# RelayArray.net
KiCad netlist of a schematic drawn in Altium Designer
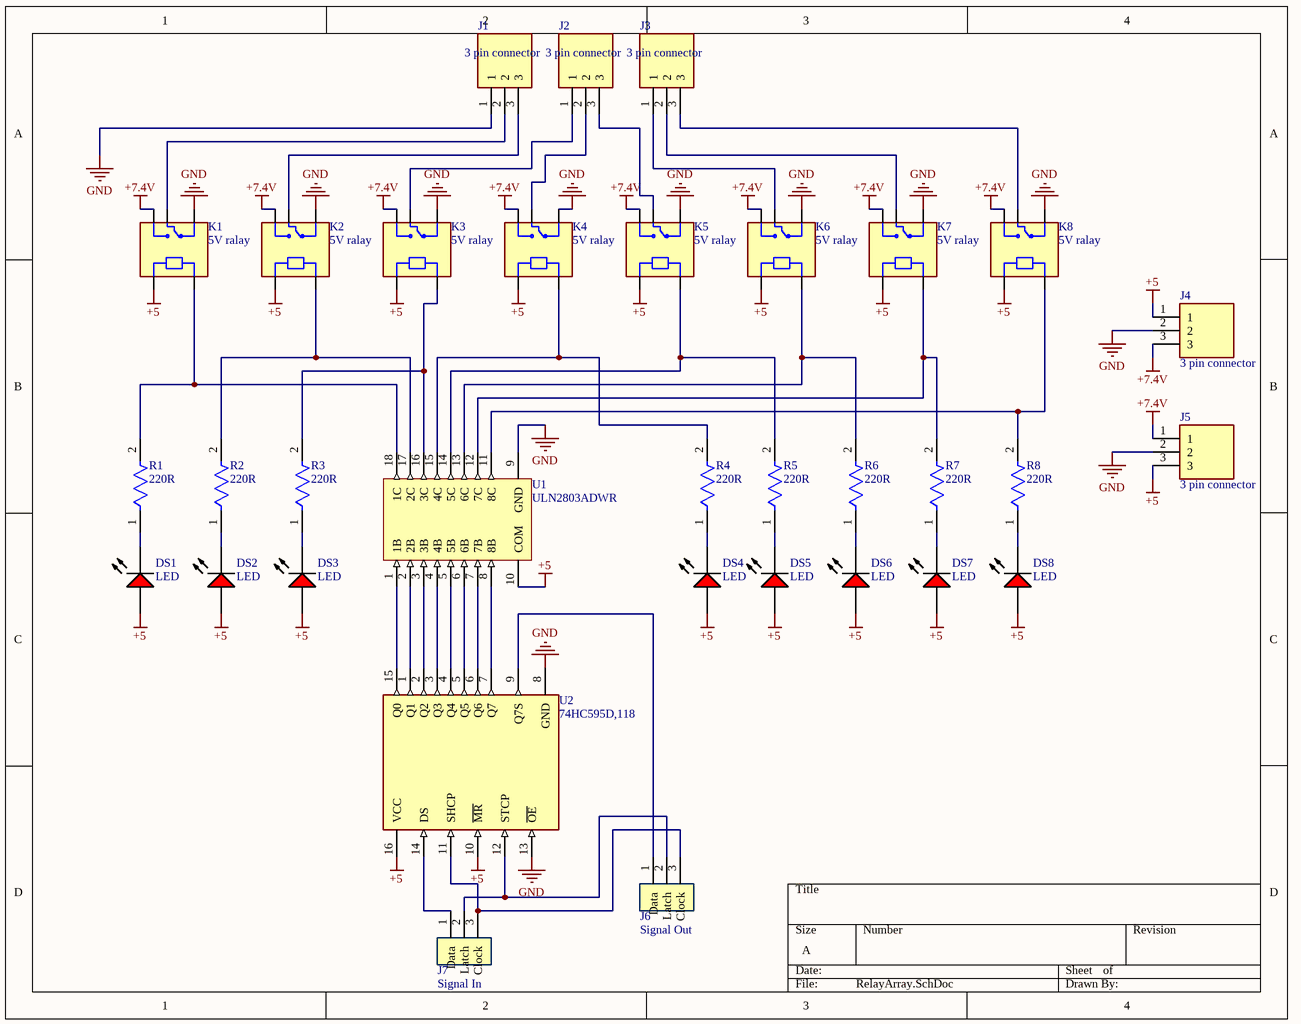
[diagram p0: RelayArray.SchDoc]

(export (version "E")
  (design (tool "Eeschema 10.0.6"))
  (components
    (comp (ref "DS1")
      (value "LED")
      (footprint "big red led")
      (description "T-1 3/4 (5 mm) Diffused LED Lamp, 1.9 V, -40 to 100 degC, 2-Pin THD, RoHS, Bulk")
      (fields (field (name "MANUFACTURER") "Avago"))
      (libsource (lib "Firework Detenator PCB") (part "big red led"))
    )
    (comp (ref "DS2")
      (value "LED")
      (footprint "big red led")
      (description "T-1 3/4 (5 mm) Diffused LED Lamp, 1.9 V, -40 to 100 degC, 2-Pin THD, RoHS, Bulk")
      (fields (field (name "MANUFACTURER") "Avago"))
      (libsource (lib "Firework Detenator PCB") (part "big red led"))
    )
    (comp (ref "DS3")
      (value "LED")
      (footprint "big red led")
      (description "T-1 3/4 (5 mm) Diffused LED Lamp, 1.9 V, -40 to 100 degC, 2-Pin THD, RoHS, Bulk")
      (fields (field (name "MANUFACTURER") "Avago"))
      (libsource (lib "Firework Detenator PCB") (part "big red led"))
    )
    (comp (ref "DS4")
      (value "LED")
      (footprint "big red led")
      (description "T-1 3/4 (5 mm) Diffused LED Lamp, 1.9 V, -40 to 100 degC, 2-Pin THD, RoHS, Bulk")
      (fields (field (name "MANUFACTURER") "Avago"))
      (libsource (lib "Firework Detenator PCB") (part "big red led"))
    )
    (comp (ref "DS5")
      (value "LED")
      (footprint "big red led")
      (description "T-1 3/4 (5 mm) Diffused LED Lamp, 1.9 V, -40 to 100 degC, 2-Pin THD, RoHS, Bulk")
      (fields (field (name "MANUFACTURER") "Avago"))
      (libsource (lib "Firework Detenator PCB") (part "big red led"))
    )
    (comp (ref "DS6")
      (value "LED")
      (footprint "big red led")
      (description "T-1 3/4 (5 mm) Diffused LED Lamp, 1.9 V, -40 to 100 degC, 2-Pin THD, RoHS, Bulk")
      (fields (field (name "MANUFACTURER") "Avago"))
      (libsource (lib "Firework Detenator PCB") (part "big red led"))
    )
    (comp (ref "DS7")
      (value "LED")
      (footprint "big red led")
      (description "T-1 3/4 (5 mm) Diffused LED Lamp, 1.9 V, -40 to 100 degC, 2-Pin THD, RoHS, Bulk")
      (fields (field (name "MANUFACTURER") "Avago"))
      (libsource (lib "Firework Detenator PCB") (part "big red led"))
    )
    (comp (ref "DS8")
      (value "LED")
      (footprint "big red led")
      (description "T-1 3/4 (5 mm) Diffused LED Lamp, 1.9 V, -40 to 100 degC, 2-Pin THD, RoHS, Bulk")
      (fields (field (name "MANUFACTURER") "Avago"))
      (libsource (lib "Firework Detenator PCB") (part "big red led"))
    )
    (comp (ref "J1")
      (value "3 pin connector")
      (footprint "3 pin connector")
      (description "3P,STRAIGHT,SIDE ENTRY,3.5MM")
      (fields (field (name "MF") "TE Connectivity") (field (name "MP") "1546551-3"))
      (libsource (lib "") (part "3 pin connector_1"))
    )
    (comp (ref "J2")
      (value "3 pin connector")
      (footprint "3 pin connector")
      (description "3P,STRAIGHT,SIDE ENTRY,3.5MM")
      (fields (field (name "MF") "TE Connectivity") (field (name "MP") "1546551-3"))
      (libsource (lib "") (part "3 pin connector_1"))
    )
    (comp (ref "J3")
      (value "3 pin connector")
      (footprint "3 pin connector")
      (description "3P,STRAIGHT,SIDE ENTRY,3.5MM")
      (fields (field (name "MF") "TE Connectivity") (field (name "MP") "1546551-3"))
      (libsource (lib "") (part "3 pin connector_1"))
    )
    (comp (ref "J4")
      (value "3 pin connector")
      (footprint "3 pin connector")
      (description "3P,STRAIGHT,SIDE ENTRY,3.5MM")
      (fields (field (name "MF") "TE Connectivity") (field (name "MP") "1546551-3"))
      (libsource (lib "Firework Detenator PCB") (part "3 pin connector"))
    )
    (comp (ref "J5")
      (value "3 pin connector")
      (footprint "3 pin connector")
      (description "3P,STRAIGHT,SIDE ENTRY,3.5MM")
      (fields (field (name "MF") "TE Connectivity") (field (name "MP") "1546551-3"))
      (libsource (lib "Firework Detenator PCB") (part "3 pin connector"))
    )
    (comp (ref "J6")
      (value "Signal Out")
      (footprint "3 pin header")
      (description "3P,STRAIGHT,SIDE ENTRY,3.5MM")
      (fields (field (name "MF") "TE Connectivity") (field (name "MP") "1546551-3"))
      (libsource (lib "Firework Detenator PCB") (part "3 pin header"))
    )
    (comp (ref "J7")
      (value "Signal In")
      (footprint "3 pin header")
      (description "3P,STRAIGHT,SIDE ENTRY,3.5MM")
      (fields (field (name "MF") "TE Connectivity") (field (name "MP") "1546551-3"))
      (libsource (lib "Firework Detenator PCB") (part "3 pin header"))
    )
    (comp (ref "K1")
      (value "5V ralay")
      (footprint "RELAY_SRD-05VDC-SL-C")
      (fields (field (name "MF") "Songle Relay") (field (name "MP") "SRD-05VDC-SL-C"))
      (libsource (lib "Firework Detenator PCB") (part "5V ralay"))
    )
    (comp (ref "K2")
      (value "5V ralay")
      (footprint "RELAY_SRD-05VDC-SL-C")
      (fields (field (name "MF") "Songle Relay") (field (name "MP") "SRD-05VDC-SL-C"))
      (libsource (lib "Firework Detenator PCB") (part "5V ralay"))
    )
    (comp (ref "K3")
      (value "5V ralay")
      (footprint "RELAY_SRD-05VDC-SL-C")
      (fields (field (name "MF") "Songle Relay") (field (name "MP") "SRD-05VDC-SL-C"))
      (libsource (lib "Firework Detenator PCB") (part "5V ralay"))
    )
    (comp (ref "K4")
      (value "5V ralay")
      (footprint "RELAY_SRD-05VDC-SL-C")
      (fields (field (name "MF") "Songle Relay") (field (name "MP") "SRD-05VDC-SL-C"))
      (libsource (lib "Firework Detenator PCB") (part "5V ralay"))
    )
    (comp (ref "K5")
      (value "5V ralay")
      (footprint "RELAY_SRD-05VDC-SL-C")
      (fields (field (name "MF") "Songle Relay") (field (name "MP") "SRD-05VDC-SL-C"))
      (libsource (lib "Firework Detenator PCB") (part "5V ralay"))
    )
    (comp (ref "K6")
      (value "5V ralay")
      (footprint "RELAY_SRD-05VDC-SL-C")
      (fields (field (name "MF") "Songle Relay") (field (name "MP") "SRD-05VDC-SL-C"))
      (libsource (lib "Firework Detenator PCB") (part "5V ralay"))
    )
    (comp (ref "K7")
      (value "5V ralay")
      (footprint "RELAY_SRD-05VDC-SL-C")
      (fields (field (name "MF") "Songle Relay") (field (name "MP") "SRD-05VDC-SL-C"))
      (libsource (lib "Firework Detenator PCB") (part "5V ralay"))
    )
    (comp (ref "K8")
      (value "5V ralay")
      (footprint "RELAY_SRD-05VDC-SL-C")
      (fields (field (name "MF") "Songle Relay") (field (name "MP") "SRD-05VDC-SL-C"))
      (libsource (lib "Firework Detenator PCB") (part "5V ralay"))
    )
    (comp (ref "R1")
      (value "220R")
      (footprint "FP-CRCW0805-e3-IPC_A")
      (description "RES Thick Film, 220Ω, 1%, 0.125W, 100ppm/°C, 0805")
      (fields (field (name "TOLERANCE") "1%"))
      (libsource (lib "Altium Content Vault") (part "1029c3af85768c4190bb7ad29bc67b5"))
    )
    (comp (ref "R2")
      (value "220R")
      (footprint "FP-CRCW0805-e3-IPC_A")
      (description "RES Thick Film, 220Ω, 1%, 0.125W, 100ppm/°C, 0805")
      (fields (field (name "TOLERANCE") "1%"))
      (libsource (lib "Altium Content Vault") (part "1029c3af85768c4190bb7ad29bc67b5"))
    )
    (comp (ref "R3")
      (value "220R")
      (footprint "FP-CRCW0805-e3-IPC_A")
      (description "RES Thick Film, 220Ω, 1%, 0.125W, 100ppm/°C, 0805")
      (fields (field (name "TOLERANCE") "1%"))
      (libsource (lib "Altium Content Vault") (part "1029c3af85768c4190bb7ad29bc67b5"))
    )
    (comp (ref "R4")
      (value "220R")
      (footprint "FP-CRCW0805-e3-IPC_A")
      (description "RES Thick Film, 220Ω, 1%, 0.125W, 100ppm/°C, 0805")
      (fields (field (name "TOLERANCE") "1%"))
      (libsource (lib "Altium Content Vault") (part "1029c3af85768c4190bb7ad29bc67b5"))
    )
    (comp (ref "R5")
      (value "220R")
      (footprint "FP-CRCW0805-e3-IPC_A")
      (description "RES Thick Film, 220Ω, 1%, 0.125W, 100ppm/°C, 0805")
      (fields (field (name "TOLERANCE") "1%"))
      (libsource (lib "Altium Content Vault") (part "1029c3af85768c4190bb7ad29bc67b5"))
    )
    (comp (ref "R6")
      (value "220R")
      (footprint "FP-CRCW0805-e3-IPC_A")
      (description "RES Thick Film, 220Ω, 1%, 0.125W, 100ppm/°C, 0805")
      (fields (field (name "TOLERANCE") "1%"))
      (libsource (lib "Altium Content Vault") (part "1029c3af85768c4190bb7ad29bc67b5"))
    )
    (comp (ref "R7")
      (value "220R")
      (footprint "FP-CRCW0805-e3-IPC_A")
      (description "RES Thick Film, 220Ω, 1%, 0.125W, 100ppm/°C, 0805")
      (fields (field (name "TOLERANCE") "1%"))
      (libsource (lib "Altium Content Vault") (part "1029c3af85768c4190bb7ad29bc67b5"))
    )
    (comp (ref "R8")
      (value "220R")
      (footprint "FP-CRCW0805-e3-IPC_A")
      (description "RES Thick Film, 220Ω, 1%, 0.125W, 100ppm/°C, 0805")
      (fields (field (name "TOLERANCE") "1%"))
      (libsource (lib "Altium Content Vault") (part "1029c3af85768c4190bb7ad29bc67b5"))
    )
    (comp (ref "U1")
      (value "ULN2803ADWR")
      (footprint "DW0018A_L")
      (fields (field (name "MANUFACTURER") "Texas Instruments") (field (name "PARTNUMBER") "ULN2803A"))
      (libsource (lib "Altium Content Vault") (part "TI-ULN2803A-SOIC_DW-18"))
    )
    (comp (ref "U2")
      (value "74HC595D,118")
      (footprint "FP-SOT109-1-IPC_C")
      (description "IC SHIFT REGISTER 8BIT 16SOIC")
      (libsource (lib "Altium Content Vault") (part "7b153f231cfcc3ac06dee253bd56617"))
    )
  )
  (nets
    (net (code "1") (name "+5") (class "Default")
      (node (ref "DS1") (pin "1") (pinfunction "A_1") (pintype "passive"))
      (node (ref "DS2") (pin "1") (pinfunction "A_1") (pintype "passive"))
      (node (ref "DS3") (pin "1") (pinfunction "A_1") (pintype "passive"))
      (node (ref "DS4") (pin "1") (pinfunction "A_1") (pintype "passive"))
      (node (ref "DS5") (pin "1") (pinfunction "A_1") (pintype "passive"))
      (node (ref "DS6") (pin "1") (pinfunction "A_1") (pintype "passive"))
      (node (ref "DS7") (pin "1") (pinfunction "A_1") (pintype "passive"))
      (node (ref "DS8") (pin "1") (pinfunction "A_1") (pintype "passive"))
      (node (ref "J4") (pin "1") (pinfunction "1_1") (pintype "passive"))
      (node (ref "J5") (pin "3") (pinfunction "3_3") (pintype "passive"))
      (node (ref "K1") (pin "A1") (pinfunction "A1_A1") (pintype "passive"))
      (node (ref "K2") (pin "A1") (pinfunction "A1_A1") (pintype "passive"))
      (node (ref "K3") (pin "A1") (pinfunction "A1_A1") (pintype "passive"))
      (node (ref "K4") (pin "A1") (pinfunction "A1_A1") (pintype "passive"))
      (node (ref "K5") (pin "A1") (pinfunction "A1_A1") (pintype "passive"))
      (node (ref "K6") (pin "A1") (pinfunction "A1_A1") (pintype "passive"))
      (node (ref "K7") (pin "A1") (pinfunction "A1_A1") (pintype "passive"))
      (node (ref "K8") (pin "A1") (pinfunction "A1_A1") (pintype "passive"))
      (node (ref "U1") (pin "10") (pinfunction "COM_10") (pintype "passive"))
      (node (ref "U2") (pin "10") (pinfunction "~{MR}_10") (pintype "input"))
      (node (ref "U2") (pin "16") (pinfunction "VCC_16") (pintype "power_in"))
    )
    (net (code "2") (name "+7.4V") (class "Default")
      (node (ref "J4") (pin "3") (pinfunction "3_3") (pintype "passive"))
      (node (ref "J5") (pin "1") (pinfunction "1_1") (pintype "passive"))
      (node (ref "K1") (pin "NO") (pinfunction "NO_NO") (pintype "passive"))
      (node (ref "K2") (pin "NO") (pinfunction "NO_NO") (pintype "passive"))
      (node (ref "K3") (pin "NO") (pinfunction "NO_NO") (pintype "passive"))
      (node (ref "K4") (pin "NO") (pinfunction "NO_NO") (pintype "passive"))
      (node (ref "K5") (pin "NO") (pinfunction "NO_NO") (pintype "passive"))
      (node (ref "K6") (pin "NO") (pinfunction "NO_NO") (pintype "passive"))
      (node (ref "K7") (pin "NO") (pinfunction "NO_NO") (pintype "passive"))
      (node (ref "K8") (pin "NO") (pinfunction "NO_NO") (pintype "passive"))
    )
    (net (code "3") (name "GND") (class "Default")
      (node (ref "J1") (pin "1") (pinfunction "1_1") (pintype "passive"))
      (node (ref "J4") (pin "2") (pinfunction "2_2") (pintype "passive"))
      (node (ref "J5") (pin "2") (pinfunction "2_2") (pintype "passive"))
      (node (ref "K1") (pin "NC") (pinfunction "NC_NC") (pintype "passive"))
      (node (ref "K2") (pin "NC") (pinfunction "NC_NC") (pintype "passive"))
      (node (ref "K3") (pin "NC") (pinfunction "NC_NC") (pintype "passive"))
      (node (ref "K4") (pin "NC") (pinfunction "NC_NC") (pintype "passive"))
      (node (ref "K5") (pin "NC") (pinfunction "NC_NC") (pintype "passive"))
      (node (ref "K6") (pin "NC") (pinfunction "NC_NC") (pintype "passive"))
      (node (ref "K7") (pin "NC") (pinfunction "NC_NC") (pintype "passive"))
      (node (ref "K8") (pin "NC") (pinfunction "NC_NC") (pintype "passive"))
      (node (ref "U1") (pin "9") (pinfunction "GND_9") (pintype "power_in"))
      (node (ref "U2") (pin "13") (pinfunction "~{OE}_13") (pintype "input"))
      (node (ref "U2") (pin "8") (pinfunction "GND_8") (pintype "power_in"))
    )
    (net (code "4") (name "Net-(DS1-K)") (class "Default")
      (node (ref "DS1") (pin "2") (pinfunction "K_2") (pintype "passive"))
      (node (ref "R1") (pin "1") (pinfunction "1_1") (pintype "passive"))
    )
    (net (code "5") (name "Net-(DS2-K)") (class "Default")
      (node (ref "DS2") (pin "2") (pinfunction "K_2") (pintype "passive"))
      (node (ref "R2") (pin "1") (pinfunction "1_1") (pintype "passive"))
    )
    (net (code "6") (name "Net-(DS3-K)") (class "Default")
      (node (ref "DS3") (pin "2") (pinfunction "K_2") (pintype "passive"))
      (node (ref "R3") (pin "1") (pinfunction "1_1") (pintype "passive"))
    )
    (net (code "7") (name "Net-(DS4-K)") (class "Default")
      (node (ref "DS4") (pin "2") (pinfunction "K_2") (pintype "passive"))
      (node (ref "R4") (pin "1") (pinfunction "1_1") (pintype "passive"))
    )
    (net (code "8") (name "Net-(DS5-K)") (class "Default")
      (node (ref "DS5") (pin "2") (pinfunction "K_2") (pintype "passive"))
      (node (ref "R5") (pin "1") (pinfunction "1_1") (pintype "passive"))
    )
    (net (code "9") (name "Net-(DS6-K)") (class "Default")
      (node (ref "DS6") (pin "2") (pinfunction "K_2") (pintype "passive"))
      (node (ref "R6") (pin "1") (pinfunction "1_1") (pintype "passive"))
    )
    (net (code "10") (name "Net-(DS7-K)") (class "Default")
      (node (ref "DS7") (pin "2") (pinfunction "K_2") (pintype "passive"))
      (node (ref "R7") (pin "1") (pinfunction "1_1") (pintype "passive"))
    )
    (net (code "11") (name "Net-(DS8-K)") (class "Default")
      (node (ref "DS8") (pin "2") (pinfunction "K_2") (pintype "passive"))
      (node (ref "R8") (pin "1") (pinfunction "1_1") (pintype "passive"))
    )
    (net (code "12") (name "Net-(J1-Pad2)") (class "Default")
      (node (ref "J1") (pin "2") (pinfunction "2_2") (pintype "passive"))
      (node (ref "K1") (pin "COM") (pinfunction "COM_COM") (pintype "passive"))
    )
    (net (code "13") (name "Net-(J1-Pad3)") (class "Default")
      (node (ref "J1") (pin "3") (pinfunction "3_3") (pintype "passive"))
      (node (ref "K2") (pin "COM") (pinfunction "COM_COM") (pintype "passive"))
    )
    (net (code "14") (name "Net-(J2-Pad1)") (class "Default")
      (node (ref "J2") (pin "1") (pinfunction "1_1") (pintype "passive"))
      (node (ref "K3") (pin "COM") (pinfunction "COM_COM") (pintype "passive"))
    )
    (net (code "15") (name "Net-(J2-Pad2)") (class "Default")
      (node (ref "J2") (pin "2") (pinfunction "2_2") (pintype "passive"))
      (node (ref "K4") (pin "COM") (pinfunction "COM_COM") (pintype "passive"))
    )
    (net (code "16") (name "Net-(J2-Pad3)") (class "Default")
      (node (ref "J2") (pin "3") (pinfunction "3_3") (pintype "passive"))
      (node (ref "K5") (pin "COM") (pinfunction "COM_COM") (pintype "passive"))
    )
    (net (code "17") (name "Net-(J3-Pad1)") (class "Default")
      (node (ref "J3") (pin "1") (pinfunction "1_1") (pintype "passive"))
      (node (ref "K6") (pin "COM") (pinfunction "COM_COM") (pintype "passive"))
    )
    (net (code "18") (name "Net-(J3-Pad2)") (class "Default")
      (node (ref "J3") (pin "2") (pinfunction "2_2") (pintype "passive"))
      (node (ref "K7") (pin "COM") (pinfunction "COM_COM") (pintype "passive"))
    )
    (net (code "19") (name "Net-(J3-Pad3)") (class "Default")
      (node (ref "J3") (pin "3") (pinfunction "3_3") (pintype "passive"))
      (node (ref "K8") (pin "COM") (pinfunction "COM_COM") (pintype "passive"))
    )
    (net (code "20") (name "Net-(J6-Clock)") (class "Default")
      (node (ref "J6") (pin "3") (pinfunction "Clock_3") (pintype "passive"))
      (node (ref "J7") (pin "3") (pinfunction "Clock_3") (pintype "passive"))
      (node (ref "U2") (pin "11") (pinfunction "SHCP_11") (pintype "input"))
    )
    (net (code "21") (name "Net-(J6-Data)") (class "Default")
      (node (ref "J6") (pin "1") (pinfunction "Data_1") (pintype "passive"))
      (node (ref "U2") (pin "9") (pinfunction "Q7S_9") (pintype "output"))
    )
    (net (code "22") (name "Net-(J6-Latch)") (class "Default")
      (node (ref "J6") (pin "2") (pinfunction "Latch_2") (pintype "passive"))
      (node (ref "J7") (pin "2") (pinfunction "Latch_2") (pintype "passive"))
      (node (ref "U2") (pin "12") (pinfunction "STCP_12") (pintype "input"))
    )
    (net (code "23") (name "Net-(J7-Data)") (class "Default")
      (node (ref "J7") (pin "1") (pinfunction "Data_1") (pintype "passive"))
      (node (ref "U2") (pin "14") (pinfunction "DS_14") (pintype "input"))
    )
    (net (code "24") (name "Net-(U1-1B)") (class "Default")
      (node (ref "U1") (pin "1") (pinfunction "1B_1") (pintype "input"))
      (node (ref "U2") (pin "15") (pinfunction "Q0_15") (pintype "output"))
    )
    (net (code "25") (name "Net-(U1-1C)") (class "Default")
      (node (ref "K1") (pin "A2") (pinfunction "A2_A2") (pintype "passive"))
      (node (ref "R1") (pin "2") (pinfunction "2_2") (pintype "passive"))
      (node (ref "U1") (pin "18") (pinfunction "1C_18") (pintype "output"))
    )
    (net (code "26") (name "Net-(U1-2B)") (class "Default")
      (node (ref "U1") (pin "2") (pinfunction "2B_2") (pintype "input"))
      (node (ref "U2") (pin "1") (pinfunction "Q1_1") (pintype "output"))
    )
    (net (code "27") (name "Net-(U1-2C)") (class "Default")
      (node (ref "K2") (pin "A2") (pinfunction "A2_A2") (pintype "passive"))
      (node (ref "R2") (pin "2") (pinfunction "2_2") (pintype "passive"))
      (node (ref "U1") (pin "17") (pinfunction "2C_17") (pintype "output"))
    )
    (net (code "28") (name "Net-(U1-3B)") (class "Default")
      (node (ref "U1") (pin "3") (pinfunction "3B_3") (pintype "input"))
      (node (ref "U2") (pin "2") (pinfunction "Q2_2") (pintype "output"))
    )
    (net (code "29") (name "Net-(U1-3C)") (class "Default")
      (node (ref "K3") (pin "A2") (pinfunction "A2_A2") (pintype "passive"))
      (node (ref "R3") (pin "2") (pinfunction "2_2") (pintype "passive"))
      (node (ref "U1") (pin "16") (pinfunction "3C_16") (pintype "output"))
    )
    (net (code "30") (name "Net-(U1-4B)") (class "Default")
      (node (ref "U1") (pin "4") (pinfunction "4B_4") (pintype "input"))
      (node (ref "U2") (pin "3") (pinfunction "Q3_3") (pintype "output"))
    )
    (net (code "31") (name "Net-(U1-4C)") (class "Default")
      (node (ref "K4") (pin "A2") (pinfunction "A2_A2") (pintype "passive"))
      (node (ref "R4") (pin "2") (pinfunction "2_2") (pintype "passive"))
      (node (ref "U1") (pin "15") (pinfunction "4C_15") (pintype "output"))
    )
    (net (code "32") (name "Net-(U1-5B)") (class "Default")
      (node (ref "U1") (pin "5") (pinfunction "5B_5") (pintype "input"))
      (node (ref "U2") (pin "4") (pinfunction "Q4_4") (pintype "output"))
    )
    (net (code "33") (name "Net-(U1-5C)") (class "Default")
      (node (ref "K5") (pin "A2") (pinfunction "A2_A2") (pintype "passive"))
      (node (ref "R5") (pin "2") (pinfunction "2_2") (pintype "passive"))
      (node (ref "U1") (pin "14") (pinfunction "5C_14") (pintype "output"))
    )
    (net (code "34") (name "Net-(U1-6B)") (class "Default")
      (node (ref "U1") (pin "6") (pinfunction "6B_6") (pintype "input"))
      (node (ref "U2") (pin "5") (pinfunction "Q5_5") (pintype "output"))
    )
    (net (code "35") (name "Net-(U1-6C)") (class "Default")
      (node (ref "K6") (pin "A2") (pinfunction "A2_A2") (pintype "passive"))
      (node (ref "R6") (pin "2") (pinfunction "2_2") (pintype "passive"))
      (node (ref "U1") (pin "13") (pinfunction "6C_13") (pintype "output"))
    )
    (net (code "36") (name "Net-(U1-7B)") (class "Default")
      (node (ref "U1") (pin "7") (pinfunction "7B_7") (pintype "input"))
      (node (ref "U2") (pin "6") (pinfunction "Q6_6") (pintype "output"))
    )
    (net (code "37") (name "Net-(U1-7C)") (class "Default")
      (node (ref "K7") (pin "A2") (pinfunction "A2_A2") (pintype "passive"))
      (node (ref "R7") (pin "2") (pinfunction "2_2") (pintype "passive"))
      (node (ref "U1") (pin "12") (pinfunction "7C_12") (pintype "output"))
    )
    (net (code "38") (name "Net-(U1-8B)") (class "Default")
      (node (ref "U1") (pin "8") (pinfunction "8B_8") (pintype "input"))
      (node (ref "U2") (pin "7") (pinfunction "Q7_7") (pintype "output"))
    )
    (net (code "39") (name "Net-(U1-8C)") (class "Default")
      (node (ref "K8") (pin "A2") (pinfunction "A2_A2") (pintype "passive"))
      (node (ref "R8") (pin "2") (pinfunction "2_2") (pintype "passive"))
      (node (ref "U1") (pin "11") (pinfunction "8C_11") (pintype "output"))
    )
  )
)
